# BiphasicBoardv2.net
KiCad netlist of a schematic drawn in EAGLE
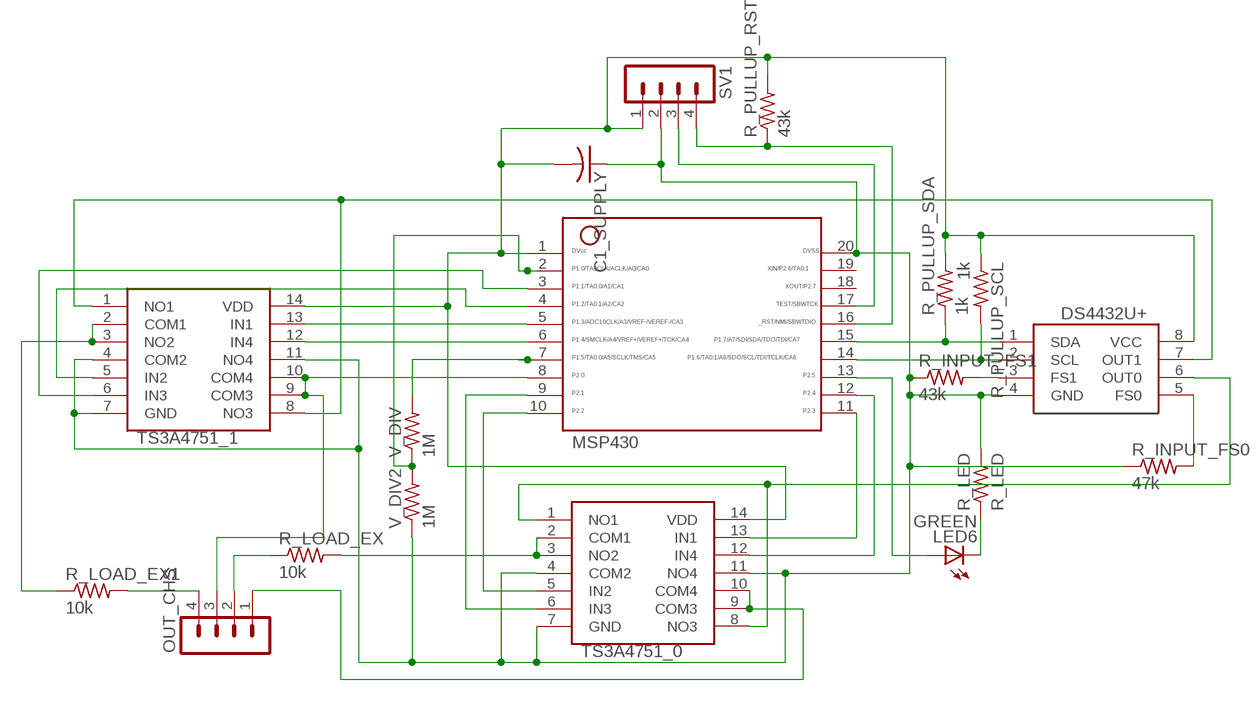
[diagram p0: schematic, sheet 1]

(export (version "E")
  (design (tool "Eeschema 10.0.6"))
  (components
    (comp (ref "C1_SUPPLY")
      (value "C-USC0603")
      (footprint "eagle-import:C0603")
      (libsource (lib "eagle-import") (part "C-USC0603"))
    )
    (comp (ref "DS4432U+")
      (value "DS4432U+")
      (footprint "eagle-import:8_PIN")
      (libsource (lib "eagle-import") (part "DS4432U+"))
    )
    (comp (ref "LED6")
      (value "GREEN")
      (footprint "eagle-import:LED-1206")
      (libsource (lib "eagle-import") (part "LED1206"))
    )
    (comp (ref "MSP430")
      (value "MSP430")
      (footprint "eagle-import:20_PIN")
      (libsource (lib "eagle-import") (part "MSP430"))
    )
    (comp (ref "OUT_CHS")
      (value "MA04-1")
      (footprint "eagle-import:MA04-1")
      (libsource (lib "eagle-import") (part "MA04-1"))
    )
    (comp (ref "R_INPUT_FS0")
      (value "47k")
      (footprint "eagle-import:R0603")
      (libsource (lib "eagle-import") (part "R-US_R0603"))
    )
    (comp (ref "R_INPUT_FS1")
      (value "43k")
      (footprint "eagle-import:R0603")
      (libsource (lib "eagle-import") (part "R-US_R0603"))
    )
    (comp (ref "R_LED")
      (value "R_LED")
      (footprint "eagle-import:R0603")
      (libsource (lib "eagle-import") (part "R-US_R0603"))
    )
    (comp (ref "R_LOAD_EX")
      (value "10k")
      (footprint "eagle-import:R0603")
      (libsource (lib "eagle-import") (part "R-US_R0603"))
    )
    (comp (ref "R_LOAD_EX1")
      (value "10k")
      (footprint "eagle-import:R0603")
      (libsource (lib "eagle-import") (part "R-US_R0603"))
    )
    (comp (ref "R_PULLUP_RST")
      (value "43k")
      (footprint "eagle-import:R0603")
      (libsource (lib "eagle-import") (part "R-US_R0603"))
    )
    (comp (ref "R_PULLUP_SCL")
      (value "1k")
      (footprint "eagle-import:R0603")
      (libsource (lib "eagle-import") (part "R-US_R0603"))
    )
    (comp (ref "R_PULLUP_SDA")
      (value "1k")
      (footprint "eagle-import:R0603")
      (libsource (lib "eagle-import") (part "R-US_R0603"))
    )
    (comp (ref "SV1")
      (value "MA04-1")
      (footprint "eagle-import:MA04-1")
      (libsource (lib "eagle-import") (part "MA04-1"))
    )
    (comp (ref "TS3A4751_0")
      (value "TS3A4751")
      (footprint "eagle-import:14_PIN")
      (libsource (lib "eagle-import") (part "TS3A4751"))
    )
    (comp (ref "TS3A4751_1")
      (value "TS3A4751")
      (footprint "eagle-import:14_PIN")
      (libsource (lib "eagle-import") (part "TS3A4751"))
    )
    (comp (ref "V_DIV")
      (value "1M")
      (footprint "eagle-import:R0603")
      (libsource (lib "eagle-import") (part "R-US_R0603"))
    )
    (comp (ref "V_DIV2")
      (value "1M")
      (footprint "eagle-import:R0603")
      (libsource (lib "eagle-import") (part "R-US_R0603"))
    )
  )
  (nets
    (net (code "1") (name "Net-(DS4432U+-FS0)") (class "Default")
      (node (ref "DS4432U+") (pin "5") (pinfunction "FS0_5") (pintype "bidirectional"))
      (node (ref "R_INPUT_FS0") (pin "2") (pinfunction "2_2") (pintype "passive"))
    )
    (net (code "2") (name "Net-(DS4432U+-FS1)") (class "Default")
      (node (ref "DS4432U+") (pin "3") (pinfunction "FS1_3") (pintype "bidirectional"))
      (node (ref "R_INPUT_FS1") (pin "2") (pinfunction "2_2") (pintype "passive"))
    )
    (net (code "3") (name "Net-(DS4432U+-GND)") (class "Default")
      (node (ref "C1_SUPPLY") (pin "1") (pinfunction "1_1") (pintype "passive"))
      (node (ref "DS4432U+") (pin "4") (pinfunction "GND_4") (pintype "bidirectional"))
      (node (ref "MSP430") (pin "20") (pinfunction "20_20") (pintype "bidirectional"))
      (node (ref "R_INPUT_FS0") (pin "1") (pinfunction "1_1") (pintype "passive"))
      (node (ref "R_INPUT_FS1") (pin "1") (pinfunction "1_1") (pintype "passive"))
      (node (ref "R_LED") (pin "2") (pinfunction "2_2") (pintype "passive"))
      (node (ref "SV1") (pin "2") (pinfunction "2_2") (pintype "passive"))
      (node (ref "TS3A4751_0") (pin "11") (pinfunction "NO4_11") (pintype "bidirectional"))
      (node (ref "TS3A4751_0") (pin "4") (pinfunction "COM2_4") (pintype "bidirectional"))
      (node (ref "TS3A4751_0") (pin "7") (pinfunction "GND_7") (pintype "bidirectional"))
      (node (ref "TS3A4751_1") (pin "11") (pinfunction "NO4_11") (pintype "bidirectional"))
      (node (ref "TS3A4751_1") (pin "4") (pinfunction "COM2_4") (pintype "bidirectional"))
      (node (ref "TS3A4751_1") (pin "7") (pinfunction "GND_7") (pintype "bidirectional"))
      (node (ref "V_DIV2") (pin "1") (pinfunction "1_1") (pintype "passive"))
    )
    (net (code "4") (name "Net-(DS4432U+-OUT0)") (class "Default")
      (node (ref "DS4432U+") (pin "6") (pinfunction "OUT0_6") (pintype "bidirectional"))
      (node (ref "TS3A4751_0") (pin "1") (pinfunction "NO1_1") (pintype "bidirectional"))
      (node (ref "TS3A4751_0") (pin "8") (pinfunction "NO3_8") (pintype "bidirectional"))
    )
    (net (code "5") (name "Net-(DS4432U+-OUT1)") (class "Default")
      (node (ref "DS4432U+") (pin "7") (pinfunction "OUT1_7") (pintype "bidirectional"))
      (node (ref "TS3A4751_1") (pin "1") (pinfunction "NO1_1") (pintype "bidirectional"))
      (node (ref "TS3A4751_1") (pin "8") (pinfunction "NO3_8") (pintype "bidirectional"))
    )
    (net (code "6") (name "Net-(DS4432U+-SCL)") (class "Default")
      (node (ref "DS4432U+") (pin "2") (pinfunction "SCL_2") (pintype "bidirectional"))
      (node (ref "MSP430") (pin "14") (pinfunction "14_14") (pintype "bidirectional"))
      (node (ref "R_PULLUP_SCL") (pin "2") (pinfunction "2_2") (pintype "passive"))
    )
    (net (code "7") (name "Net-(DS4432U+-SDA)") (class "Default")
      (node (ref "DS4432U+") (pin "1") (pinfunction "SDA_1") (pintype "bidirectional"))
      (node (ref "MSP430") (pin "15") (pinfunction "15_15") (pintype "bidirectional"))
      (node (ref "R_PULLUP_SDA") (pin "1") (pinfunction "1_1") (pintype "passive"))
    )
    (net (code "8") (name "Net-(DS4432U+-VCC)") (class "Default")
      (node (ref "C1_SUPPLY") (pin "2") (pinfunction "2_2") (pintype "passive"))
      (node (ref "DS4432U+") (pin "8") (pinfunction "VCC_8") (pintype "bidirectional"))
      (node (ref "MSP430") (pin "1") (pinfunction "1_1") (pintype "bidirectional"))
      (node (ref "R_PULLUP_RST") (pin "2") (pinfunction "2_2") (pintype "passive"))
      (node (ref "R_PULLUP_SCL") (pin "1") (pinfunction "1_1") (pintype "passive"))
      (node (ref "R_PULLUP_SDA") (pin "2") (pinfunction "2_2") (pintype "passive"))
      (node (ref "SV1") (pin "1") (pinfunction "1_1") (pintype "passive"))
      (node (ref "TS3A4751_0") (pin "14") (pinfunction "VDD_14") (pintype "bidirectional"))
      (node (ref "TS3A4751_1") (pin "14") (pinfunction "VDD_14") (pintype "bidirectional"))
    )
    (net (code "9") (name "Net-(LED6-PadA)") (class "Default")
      (node (ref "LED6") (pin "A") (pinfunction "A_A") (pintype "passive"))
      (node (ref "MSP430") (pin "13") (pinfunction "13_13") (pintype "bidirectional"))
    )
    (net (code "10") (name "Net-(LED6-PadC)") (class "Default")
      (node (ref "LED6") (pin "C") (pinfunction "C_C") (pintype "passive"))
      (node (ref "R_LED") (pin "1") (pinfunction "1_1") (pintype "passive"))
    )
    (net (code "11") (name "Net-(MSP430-Pad2)") (class "Default")
      (node (ref "MSP430") (pin "2") (pinfunction "2_2") (pintype "bidirectional"))
      (node (ref "V_DIV") (pin "1") (pinfunction "1_1") (pintype "passive"))
      (node (ref "V_DIV2") (pin "2") (pinfunction "2_2") (pintype "passive"))
    )
    (net (code "12") (name "Net-(MSP430-Pad7)") (class "Default")
      (node (ref "MSP430") (pin "7") (pinfunction "7_7") (pintype "bidirectional"))
      (node (ref "V_DIV") (pin "2") (pinfunction "2_2") (pintype "passive"))
    )
    (net (code "13") (name "Net-(MSP430-Pad16)") (class "Default")
      (node (ref "MSP430") (pin "16") (pinfunction "16_16") (pintype "bidirectional"))
      (node (ref "R_PULLUP_RST") (pin "1") (pinfunction "1_1") (pintype "passive"))
      (node (ref "SV1") (pin "4") (pinfunction "4_4") (pintype "passive"))
    )
    (net (code "14") (name "Net-(MSP430-Pad17)") (class "Default")
      (node (ref "MSP430") (pin "17") (pinfunction "17_17") (pintype "bidirectional"))
      (node (ref "SV1") (pin "3") (pinfunction "3_3") (pintype "passive"))
    )
    (net (code "15") (name "Net-(OUT_CHS-Pad2)") (class "Default")
      (node (ref "OUT_CHS") (pin "2") (pinfunction "2_2") (pintype "passive"))
      (node (ref "R_LOAD_EX") (pin "1") (pinfunction "1_1") (pintype "passive"))
    )
    (net (code "16") (name "Net-(OUT_CHS-Pad4)") (class "Default")
      (node (ref "OUT_CHS") (pin "4") (pinfunction "4_4") (pintype "passive"))
      (node (ref "R_LOAD_EX1") (pin "2") (pinfunction "2_2") (pintype "passive"))
    )
    (net (code "17") (name "Net-(TS3A4751_0-COM1)") (class "Default")
      (node (ref "R_LOAD_EX") (pin "2") (pinfunction "2_2") (pintype "passive"))
      (node (ref "TS3A4751_0") (pin "2") (pinfunction "COM1_2") (pintype "bidirectional"))
      (node (ref "TS3A4751_0") (pin "3") (pinfunction "NO2_3") (pintype "bidirectional"))
    )
    (net (code "18") (name "Net-(TS3A4751_0-COM3)") (class "Default")
      (node (ref "OUT_CHS") (pin "1") (pinfunction "1_1") (pintype "passive"))
      (node (ref "TS3A4751_0") (pin "10") (pinfunction "COM4_10") (pintype "bidirectional"))
      (node (ref "TS3A4751_0") (pin "9") (pinfunction "COM3_9") (pintype "bidirectional"))
    )
    (net (code "19") (name "Net-(TS3A4751_0-IN1)") (class "Default")
      (node (ref "MSP430") (pin "11") (pinfunction "11_11") (pintype "bidirectional"))
      (node (ref "TS3A4751_0") (pin "13") (pinfunction "IN1_13") (pintype "bidirectional"))
    )
    (net (code "20") (name "Net-(TS3A4751_0-IN2)") (class "Default")
      (node (ref "MSP430") (pin "10") (pinfunction "10_10") (pintype "bidirectional"))
      (node (ref "TS3A4751_0") (pin "5") (pinfunction "IN2_5") (pintype "bidirectional"))
    )
    (net (code "21") (name "Net-(TS3A4751_0-IN3)") (class "Default")
      (node (ref "MSP430") (pin "9") (pinfunction "9_9") (pintype "bidirectional"))
      (node (ref "TS3A4751_0") (pin "6") (pinfunction "IN3_6") (pintype "bidirectional"))
    )
    (net (code "22") (name "Net-(TS3A4751_0-IN4)") (class "Default")
      (node (ref "MSP430") (pin "12") (pinfunction "12_12") (pintype "bidirectional"))
      (node (ref "TS3A4751_0") (pin "12") (pinfunction "IN4_12") (pintype "bidirectional"))
    )
    (net (code "23") (name "Net-(TS3A4751_1-COM1)") (class "Default")
      (node (ref "R_LOAD_EX1") (pin "1") (pinfunction "1_1") (pintype "passive"))
      (node (ref "TS3A4751_1") (pin "2") (pinfunction "COM1_2") (pintype "bidirectional"))
      (node (ref "TS3A4751_1") (pin "3") (pinfunction "NO2_3") (pintype "bidirectional"))
    )
    (net (code "24") (name "Net-(TS3A4751_1-COM3)") (class "Default")
      (node (ref "MSP430") (pin "8") (pinfunction "8_8") (pintype "bidirectional"))
      (node (ref "OUT_CHS") (pin "3") (pinfunction "3_3") (pintype "passive"))
      (node (ref "TS3A4751_1") (pin "10") (pinfunction "COM4_10") (pintype "bidirectional"))
      (node (ref "TS3A4751_1") (pin "9") (pinfunction "COM3_9") (pintype "bidirectional"))
    )
    (net (code "25") (name "Net-(TS3A4751_1-IN1)") (class "Default")
      (node (ref "MSP430") (pin "5") (pinfunction "5_5") (pintype "bidirectional"))
      (node (ref "TS3A4751_1") (pin "13") (pinfunction "IN1_13") (pintype "bidirectional"))
    )
    (net (code "26") (name "Net-(TS3A4751_1-IN2)") (class "Default")
      (node (ref "MSP430") (pin "4") (pinfunction "4_4") (pintype "bidirectional"))
      (node (ref "TS3A4751_1") (pin "5") (pinfunction "IN2_5") (pintype "bidirectional"))
    )
    (net (code "27") (name "Net-(TS3A4751_1-IN3)") (class "Default")
      (node (ref "MSP430") (pin "3") (pinfunction "3_3") (pintype "bidirectional"))
      (node (ref "TS3A4751_1") (pin "6") (pinfunction "IN3_6") (pintype "bidirectional"))
    )
    (net (code "28") (name "Net-(TS3A4751_1-IN4)") (class "Default")
      (node (ref "MSP430") (pin "6") (pinfunction "6_6") (pintype "bidirectional"))
      (node (ref "TS3A4751_1") (pin "12") (pinfunction "IN4_12") (pintype "bidirectional"))
    )
    (net (code "29") (name "unconnected-(MSP430-Pad18)") (class "Default")
      (node (ref "MSP430") (pin "18") (pinfunction "18_18") (pintype "bidirectional"))
    )
    (net (code "30") (name "unconnected-(MSP430-Pad19)") (class "Default")
      (node (ref "MSP430") (pin "19") (pinfunction "19_19") (pintype "bidirectional"))
    )
  )
)
